# v2.net
KiCad netlist of a schematic drawn in EAGLE
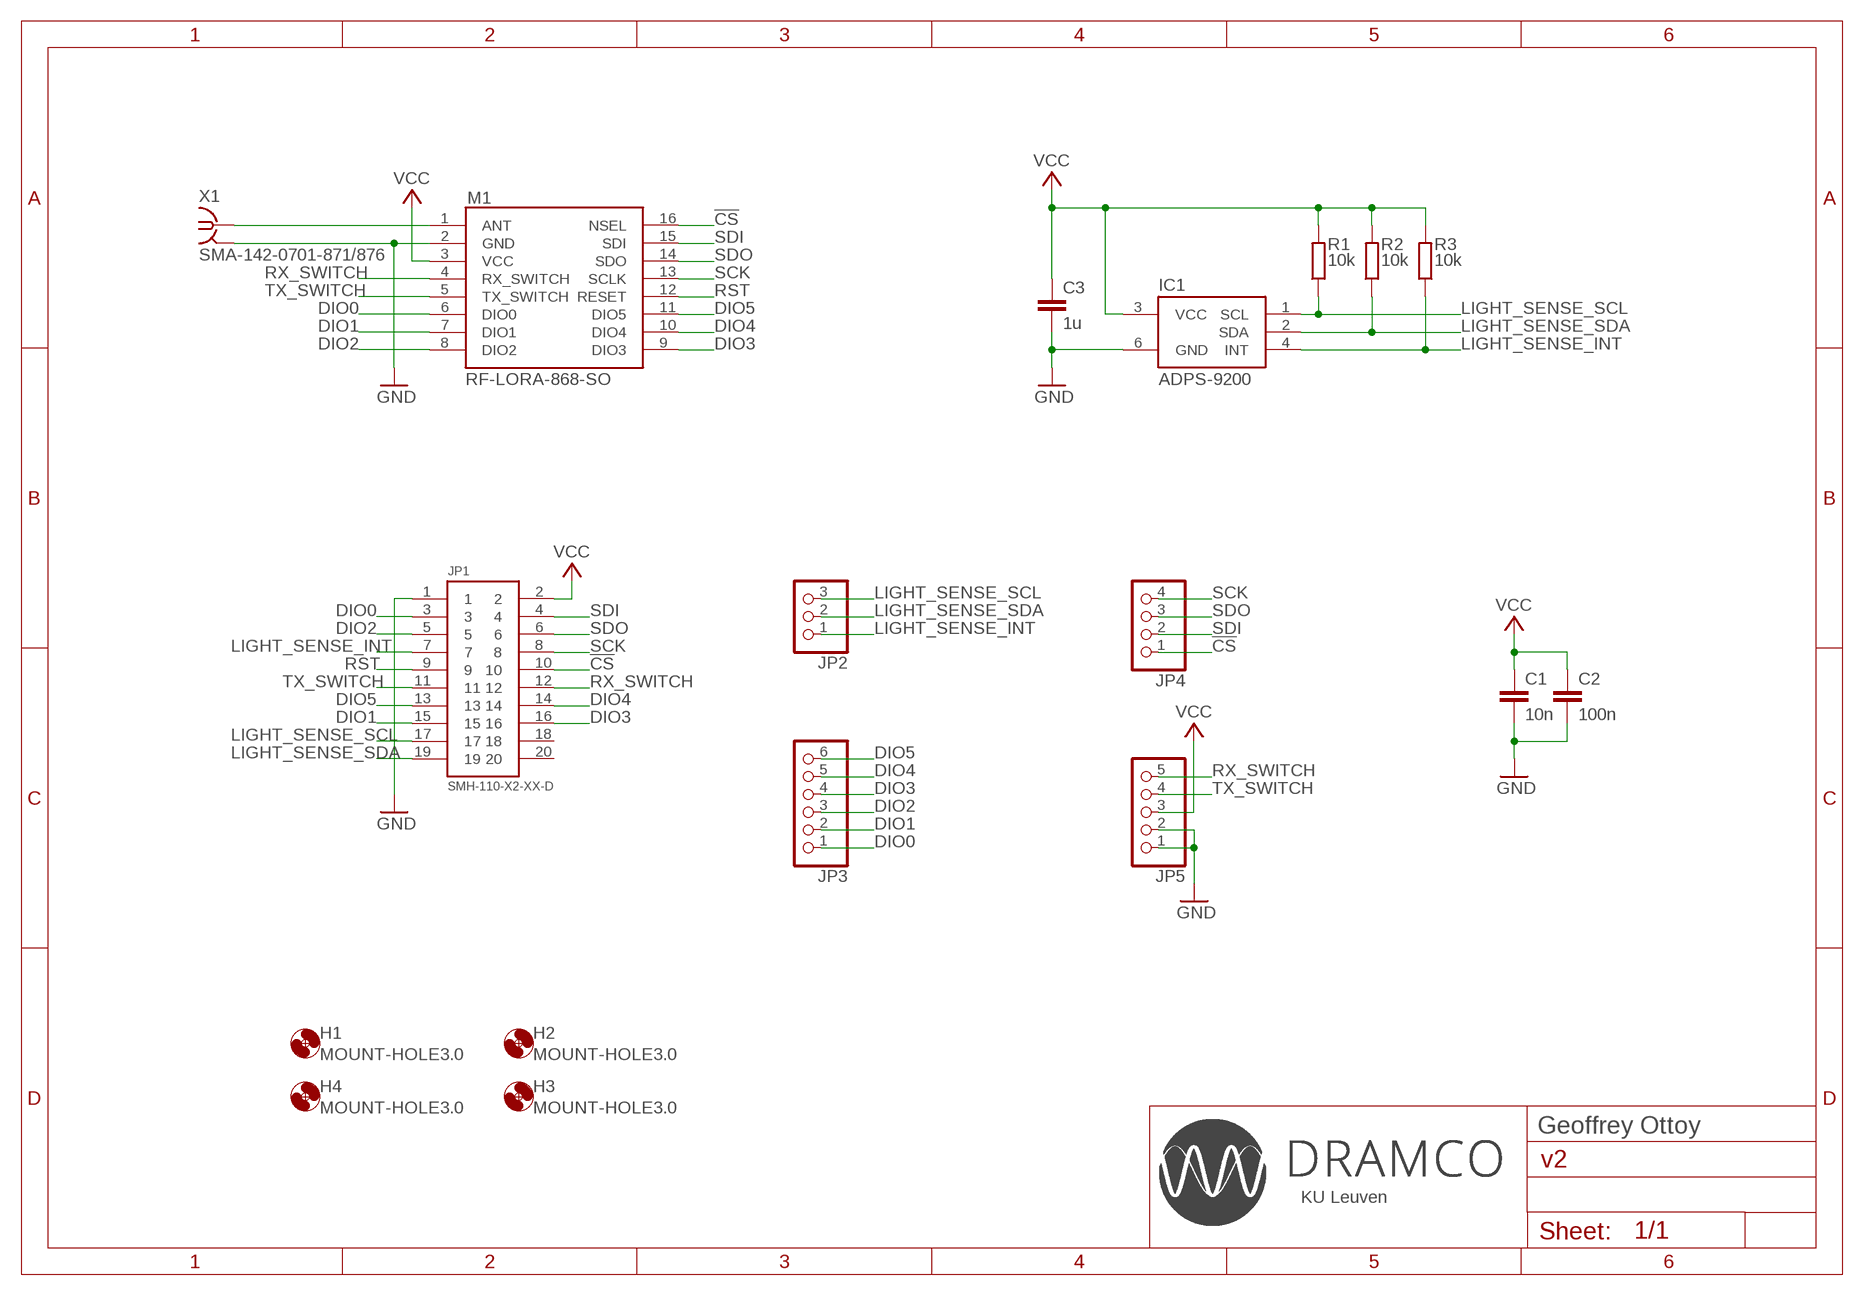
[diagram p0: schematic, sheet 1]

(export (version "E")
  (design (tool "Eeschema 10.0.6"))
  (components
    (comp (ref "C1")
      (value "10n")
      (footprint "eagle-import:C0805K")
      (libsource (lib "eagle-import") (part "C-EUC0805K"))
    )
    (comp (ref "C2")
      (value "100n")
      (footprint "eagle-import:C0805K")
      (libsource (lib "eagle-import") (part "C-EUC0805K"))
    )
    (comp (ref "C3")
      (value "1u")
      (footprint "eagle-import:C0805K")
      (libsource (lib "eagle-import") (part "C-EUC0805K"))
    )
    (comp (ref "H1")
      (value "MOUNT-HOLE3.0")
      (footprint "eagle-import:3,0")
      (libsource (lib "eagle-import") (part "MOUNT-HOLE3.0"))
    )
    (comp (ref "H2")
      (value "MOUNT-HOLE3.0")
      (footprint "eagle-import:3,0")
      (libsource (lib "eagle-import") (part "MOUNT-HOLE3.0"))
    )
    (comp (ref "H3")
      (value "MOUNT-HOLE3.0")
      (footprint "eagle-import:3,0")
      (libsource (lib "eagle-import") (part "MOUNT-HOLE3.0"))
    )
    (comp (ref "H4")
      (value "MOUNT-HOLE3.0")
      (footprint "eagle-import:3,0")
      (libsource (lib "eagle-import") (part "MOUNT-HOLE3.0"))
    )
    (comp (ref "IC1")
      (value "ADPS-9200")
      (footprint "eagle-import:ADPS-9200")
      (libsource (lib "eagle-import") (part "ADPS-9200"))
    )
    (comp (ref "JP1")
      (value "SMH-110-X2-XX-D")
      (footprint "eagle-import:SMH-110-X2-XX-D")
      (libsource (lib "eagle-import") (part "SMH-110-X2-XX-D"))
    )
    (comp (ref "JP2")
      (value "PINHD-1X3")
      (footprint "eagle-import:1X03")
      (libsource (lib "eagle-import") (part "PINHD-1X3"))
    )
    (comp (ref "JP3")
      (value "PINHD-1X6")
      (footprint "eagle-import:1X06")
      (libsource (lib "eagle-import") (part "PINHD-1X6"))
    )
    (comp (ref "JP4")
      (value "PINHD-1X4")
      (footprint "eagle-import:1X04")
      (libsource (lib "eagle-import") (part "PINHD-1X4"))
    )
    (comp (ref "JP5")
      (value "PINHD-1X5")
      (footprint "eagle-import:1X05")
      (libsource (lib "eagle-import") (part "PINHD-1X5"))
    )
    (comp (ref "M1")
      (value "RF-LORA-868-SO")
      (footprint "eagle-import:RF-LORA-868-SO")
      (libsource (lib "eagle-import") (part "RF-LORA-868-SO"))
    )
    (comp (ref "R1")
      (value "10k")
      (footprint "eagle-import:M0805")
      (libsource (lib "eagle-import") (part "R-EU_M0805"))
    )
    (comp (ref "R2")
      (value "10k")
      (footprint "eagle-import:M0805")
      (libsource (lib "eagle-import") (part "R-EU_M0805"))
    )
    (comp (ref "R3")
      (value "10k")
      (footprint "eagle-import:M0805")
      (libsource (lib "eagle-import") (part "R-EU_M0805"))
    )
    (comp (ref "X1")
      (value "SMA-142-0701-871/876")
      (footprint "eagle-import:J502-ND-142-0701-871_876")
      (fields (field (name "MF") "JOHNSON COMPONENTS") (field (name "MPN") "142-0701-871"))
      (libsource (lib "eagle-import") (part "SMA-142-0701-871/876"))
    )
  )
  (nets
    (net (code "1") (name "/DIO0") (class "Default")
      (node (ref "JP1") (pin "3") (pinfunction "3_3") (pintype "bidirectional"))
      (node (ref "JP3") (pin "1") (pinfunction "1_1") (pintype "passive"))
      (node (ref "M1") (pin "6") (pinfunction "DIO0_6") (pintype "bidirectional"))
    )
    (net (code "2") (name "/DIO1") (class "Default")
      (node (ref "JP1") (pin "15") (pinfunction "15_15") (pintype "bidirectional"))
      (node (ref "JP3") (pin "2") (pinfunction "2_2") (pintype "passive"))
      (node (ref "M1") (pin "7") (pinfunction "DIO1_7") (pintype "bidirectional"))
    )
    (net (code "3") (name "/DIO2") (class "Default")
      (node (ref "JP1") (pin "5") (pinfunction "5_5") (pintype "bidirectional"))
      (node (ref "JP3") (pin "3") (pinfunction "3_3") (pintype "passive"))
      (node (ref "M1") (pin "8") (pinfunction "DIO2_8") (pintype "bidirectional"))
    )
    (net (code "4") (name "/DIO3") (class "Default")
      (node (ref "JP1") (pin "16") (pinfunction "16_16") (pintype "bidirectional"))
      (node (ref "JP3") (pin "4") (pinfunction "4_4") (pintype "passive"))
      (node (ref "M1") (pin "9") (pinfunction "DIO3_9") (pintype "bidirectional"))
    )
    (net (code "5") (name "/DIO4") (class "Default")
      (node (ref "JP1") (pin "14") (pinfunction "14_14") (pintype "bidirectional"))
      (node (ref "JP3") (pin "5") (pinfunction "5_5") (pintype "passive"))
      (node (ref "M1") (pin "10") (pinfunction "DIO4_10") (pintype "bidirectional"))
    )
    (net (code "6") (name "/DIO5") (class "Default")
      (node (ref "JP1") (pin "13") (pinfunction "13_13") (pintype "bidirectional"))
      (node (ref "JP3") (pin "6") (pinfunction "6_6") (pintype "passive"))
      (node (ref "M1") (pin "11") (pinfunction "DIO5_11") (pintype "bidirectional"))
    )
    (net (code "7") (name "/LIGHT_SENSE_INT") (class "Default")
      (node (ref "IC1") (pin "4") (pinfunction "INT_4") (pintype "bidirectional"))
      (node (ref "JP1") (pin "7") (pinfunction "7_7") (pintype "bidirectional"))
      (node (ref "JP2") (pin "1") (pinfunction "1_1") (pintype "passive"))
      (node (ref "R3") (pin "1") (pinfunction "1_1") (pintype "passive"))
    )
    (net (code "8") (name "/LIGHT_SENSE_SCL") (class "Default")
      (node (ref "IC1") (pin "1") (pinfunction "SCL_1") (pintype "bidirectional"))
      (node (ref "JP1") (pin "17") (pinfunction "17_17") (pintype "bidirectional"))
      (node (ref "JP2") (pin "3") (pinfunction "3_3") (pintype "passive"))
      (node (ref "R1") (pin "1") (pinfunction "1_1") (pintype "passive"))
    )
    (net (code "9") (name "/LIGHT_SENSE_SDA") (class "Default")
      (node (ref "IC1") (pin "2") (pinfunction "SDA_2") (pintype "bidirectional"))
      (node (ref "JP1") (pin "19") (pinfunction "19_19") (pintype "bidirectional"))
      (node (ref "JP2") (pin "2") (pinfunction "2_2") (pintype "passive"))
      (node (ref "R2") (pin "1") (pinfunction "1_1") (pintype "passive"))
    )
    (net (code "10") (name "/RST") (class "Default")
      (node (ref "JP1") (pin "9") (pinfunction "9_9") (pintype "bidirectional"))
      (node (ref "M1") (pin "12") (pinfunction "RESET_12") (pintype "bidirectional"))
    )
    (net (code "11") (name "/RX_SWITCH") (class "Default")
      (node (ref "JP1") (pin "12") (pinfunction "12_12") (pintype "bidirectional"))
      (node (ref "JP5") (pin "5") (pinfunction "5_5") (pintype "passive"))
      (node (ref "M1") (pin "4") (pinfunction "RX_SWITCH_4") (pintype "bidirectional"))
    )
    (net (code "12") (name "/SCK") (class "Default")
      (node (ref "JP1") (pin "8") (pinfunction "8_8") (pintype "bidirectional"))
      (node (ref "JP4") (pin "4") (pinfunction "4_4") (pintype "passive"))
      (node (ref "M1") (pin "13") (pinfunction "SCLK_13") (pintype "bidirectional"))
    )
    (net (code "13") (name "/SDI") (class "Default")
      (node (ref "JP1") (pin "4") (pinfunction "4_4") (pintype "bidirectional"))
      (node (ref "JP4") (pin "2") (pinfunction "2_2") (pintype "passive"))
      (node (ref "M1") (pin "15") (pinfunction "SDI_15") (pintype "bidirectional"))
    )
    (net (code "14") (name "/SDO") (class "Default")
      (node (ref "JP1") (pin "6") (pinfunction "6_6") (pintype "bidirectional"))
      (node (ref "JP4") (pin "3") (pinfunction "3_3") (pintype "passive"))
      (node (ref "M1") (pin "14") (pinfunction "SDO_14") (pintype "bidirectional"))
    )
    (net (code "15") (name "/TX_SWITCH") (class "Default")
      (node (ref "JP1") (pin "11") (pinfunction "11_11") (pintype "bidirectional"))
      (node (ref "JP5") (pin "4") (pinfunction "4_4") (pintype "passive"))
      (node (ref "M1") (pin "5") (pinfunction "TX_SWITCH_5") (pintype "bidirectional"))
    )
    (net (code "16") (name "/~{CS}") (class "Default")
      (node (ref "JP1") (pin "10") (pinfunction "10_10") (pintype "bidirectional"))
      (node (ref "JP4") (pin "1") (pinfunction "1_1") (pintype "passive"))
      (node (ref "M1") (pin "16") (pinfunction "NSEL_16") (pintype "bidirectional"))
    )
    (net (code "17") (name "GND") (class "Default")
      (node (ref "C1") (pin "2") (pinfunction "2_2") (pintype "passive"))
      (node (ref "C2") (pin "2") (pinfunction "2_2") (pintype "passive"))
      (node (ref "C3") (pin "2") (pinfunction "2_2") (pintype "passive"))
      (node (ref "IC1") (pin "6") (pinfunction "GND_6") (pintype "bidirectional"))
      (node (ref "JP1") (pin "1") (pinfunction "1_1") (pintype "bidirectional"))
      (node (ref "JP5") (pin "1") (pinfunction "1_1") (pintype "passive"))
      (node (ref "JP5") (pin "2") (pinfunction "2_2") (pintype "passive"))
      (node (ref "M1") (pin "2") (pinfunction "GND_2") (pintype "bidirectional"))
      (node (ref "X1") (pin "G@1") (pinfunction "2_G@1") (pintype "passive"))
      (node (ref "X1") (pin "G@2") (pinfunction "2_G@2") (pintype "passive"))
      (node (ref "X1") (pin "G@3") (pinfunction "2_G@3") (pintype "passive"))
      (node (ref "X1") (pin "G@4") (pinfunction "2_G@4") (pintype "passive"))
    )
    (net (code "18") (name "Net-(M1-ANT)") (class "Default")
      (node (ref "M1") (pin "1") (pinfunction "ANT_1") (pintype "bidirectional"))
      (node (ref "X1") (pin "1") (pinfunction "1_1") (pintype "passive"))
    )
    (net (code "19") (name "VCC") (class "Default")
      (node (ref "C1") (pin "1") (pinfunction "1_1") (pintype "passive"))
      (node (ref "C2") (pin "1") (pinfunction "1_1") (pintype "passive"))
      (node (ref "C3") (pin "1") (pinfunction "1_1") (pintype "passive"))
      (node (ref "IC1") (pin "3") (pinfunction "VCC_3") (pintype "bidirectional"))
      (node (ref "JP1") (pin "2") (pinfunction "2_2") (pintype "bidirectional"))
      (node (ref "JP5") (pin "3") (pinfunction "3_3") (pintype "passive"))
      (node (ref "M1") (pin "3") (pinfunction "VCC_3") (pintype "bidirectional"))
      (node (ref "R1") (pin "2") (pinfunction "2_2") (pintype "passive"))
      (node (ref "R2") (pin "2") (pinfunction "2_2") (pintype "passive"))
      (node (ref "R3") (pin "2") (pinfunction "2_2") (pintype "passive"))
    )
    (net (code "20") (name "unconnected-(JP1-Pad18)") (class "Default")
      (node (ref "JP1") (pin "18") (pinfunction "18_18") (pintype "bidirectional"))
    )
    (net (code "21") (name "unconnected-(JP1-Pad20)") (class "Default")
      (node (ref "JP1") (pin "20") (pinfunction "20_20") (pintype "bidirectional"))
    )
  )
)
